# Pinscape_Pico_Expansion_Board_-_DIY_Frie.net
KiCad netlist of a schematic drawn in EAGLE
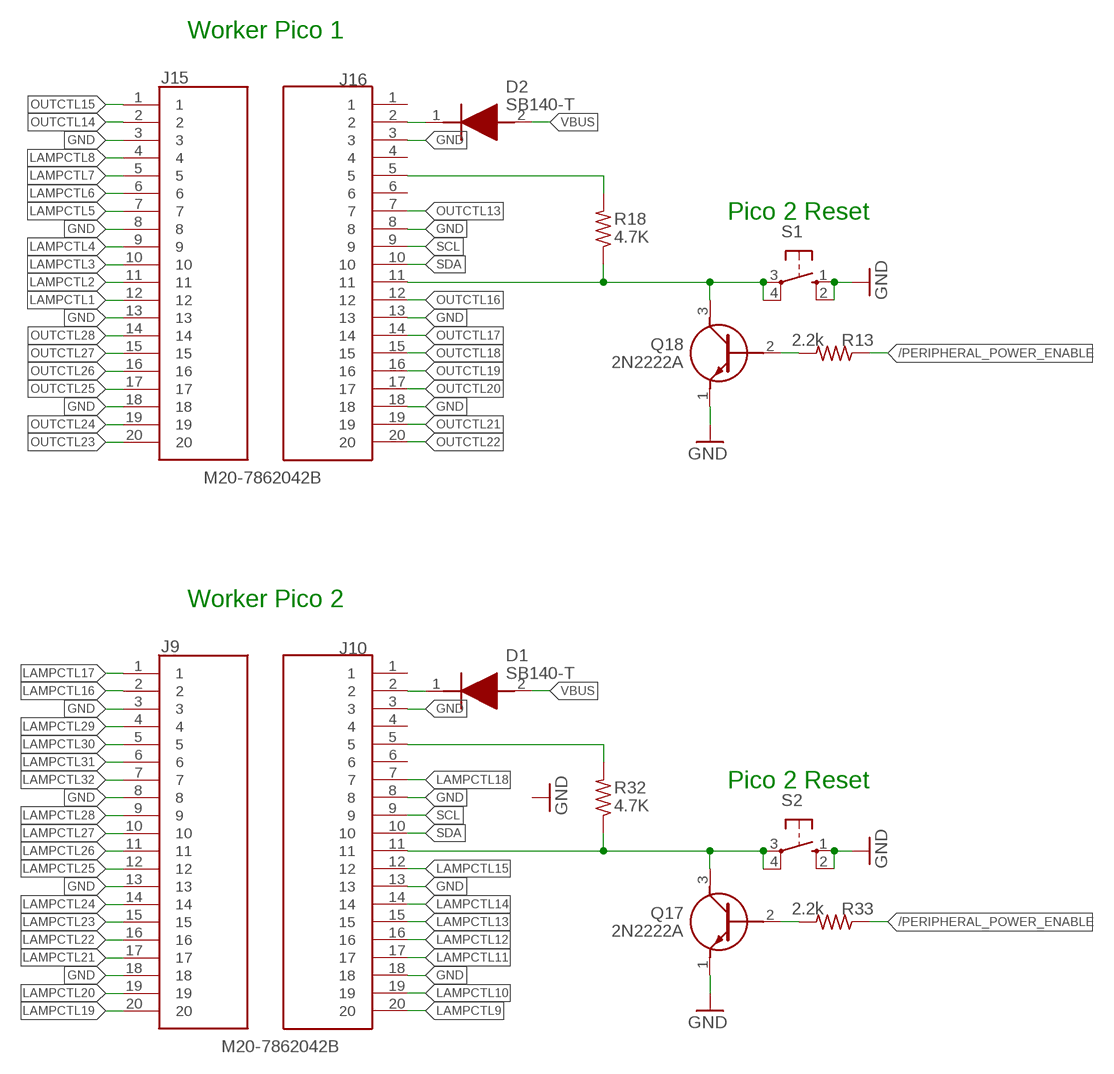
[diagram p0: schematic, sheet 1]
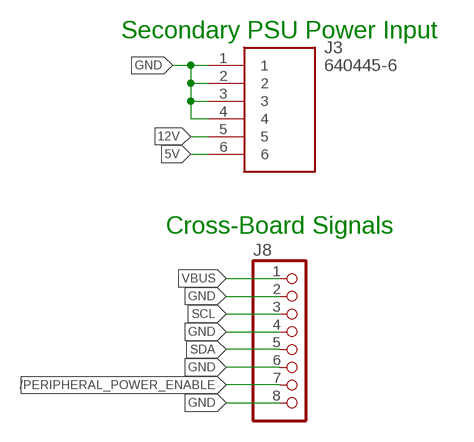
[diagram p1: schematic, sheet 2]
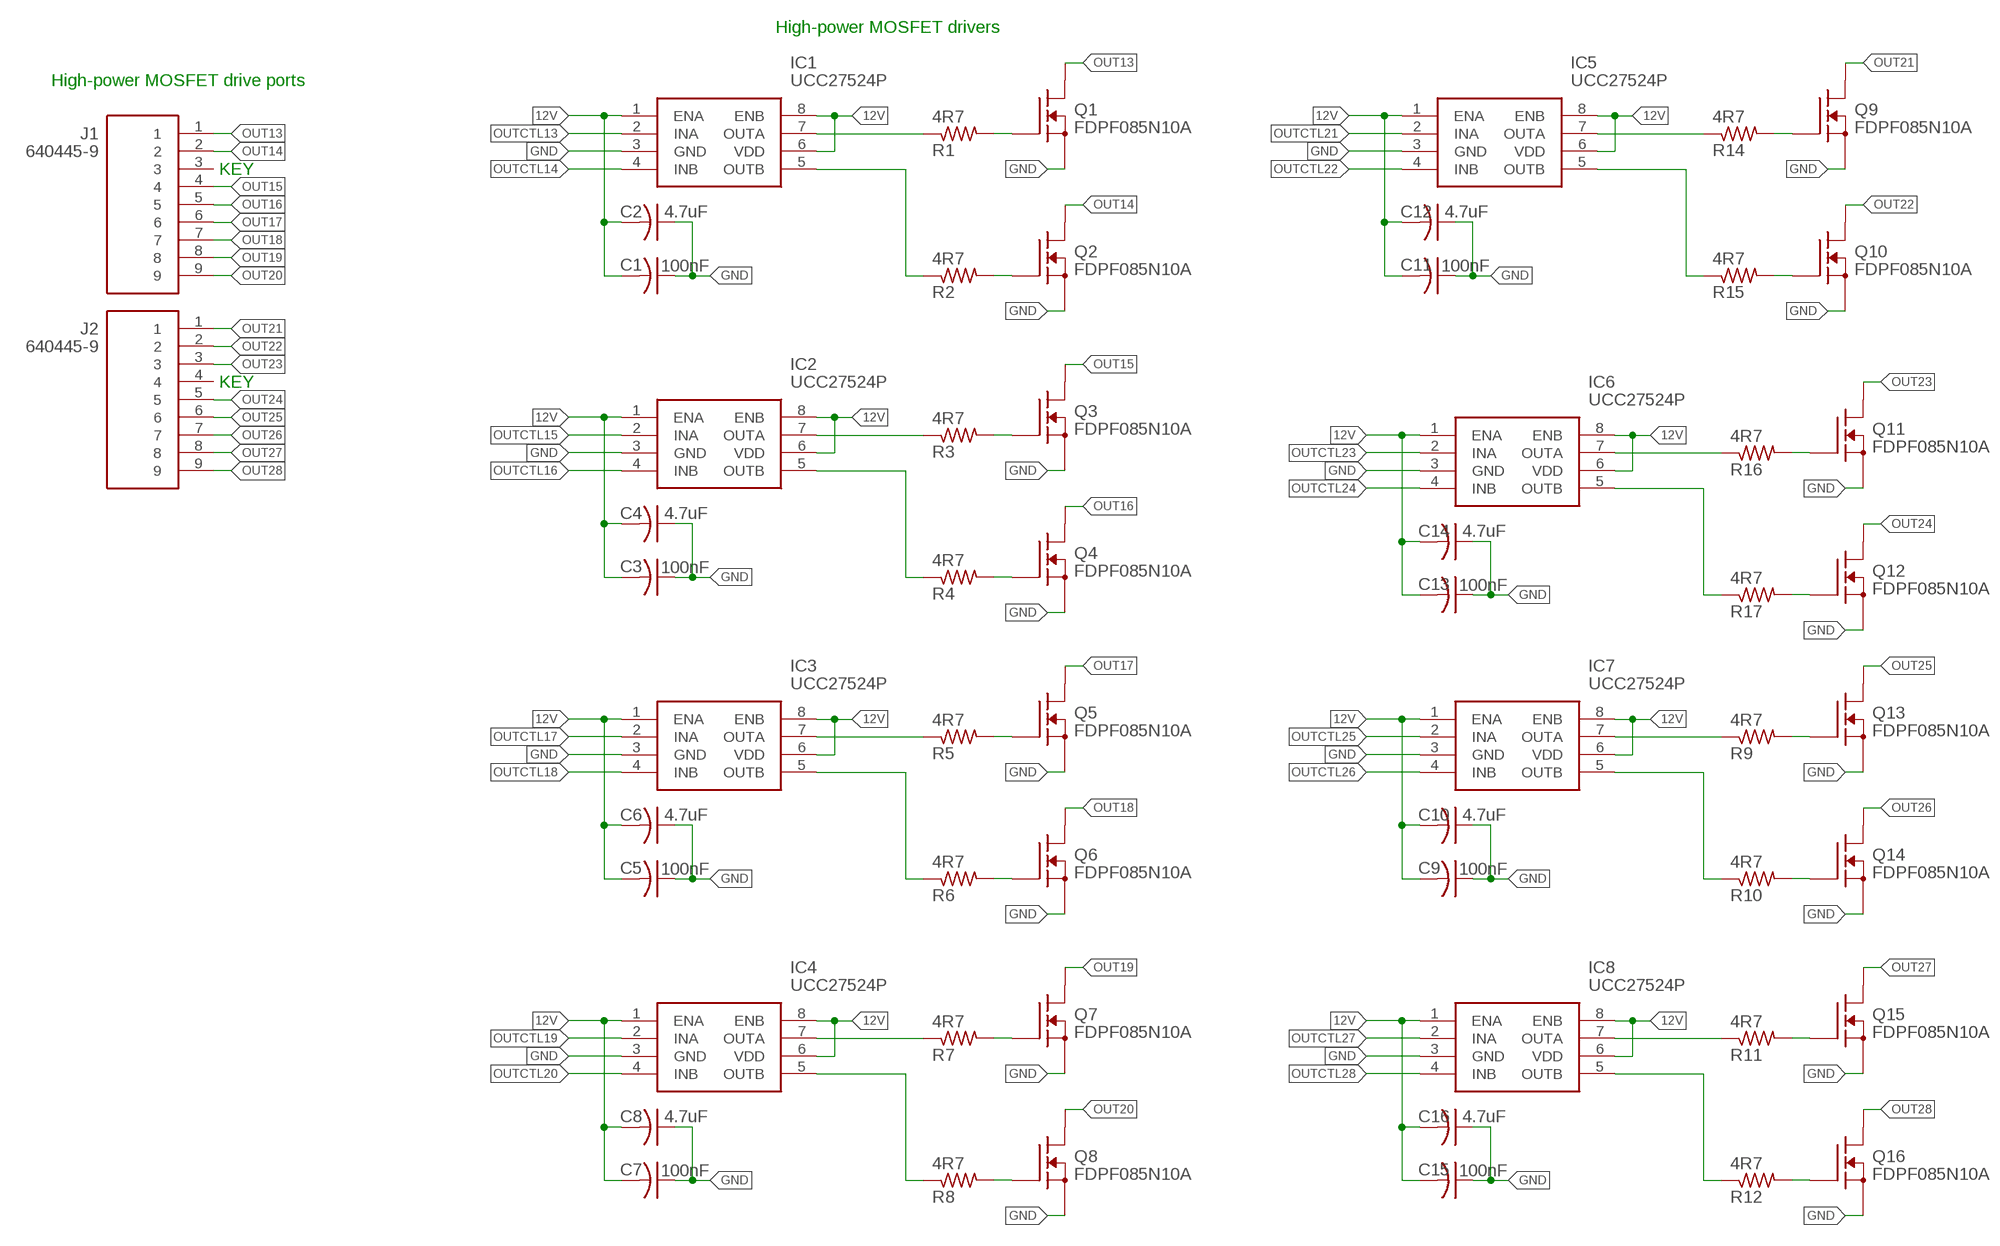
[diagram p2: schematic, sheet 3]
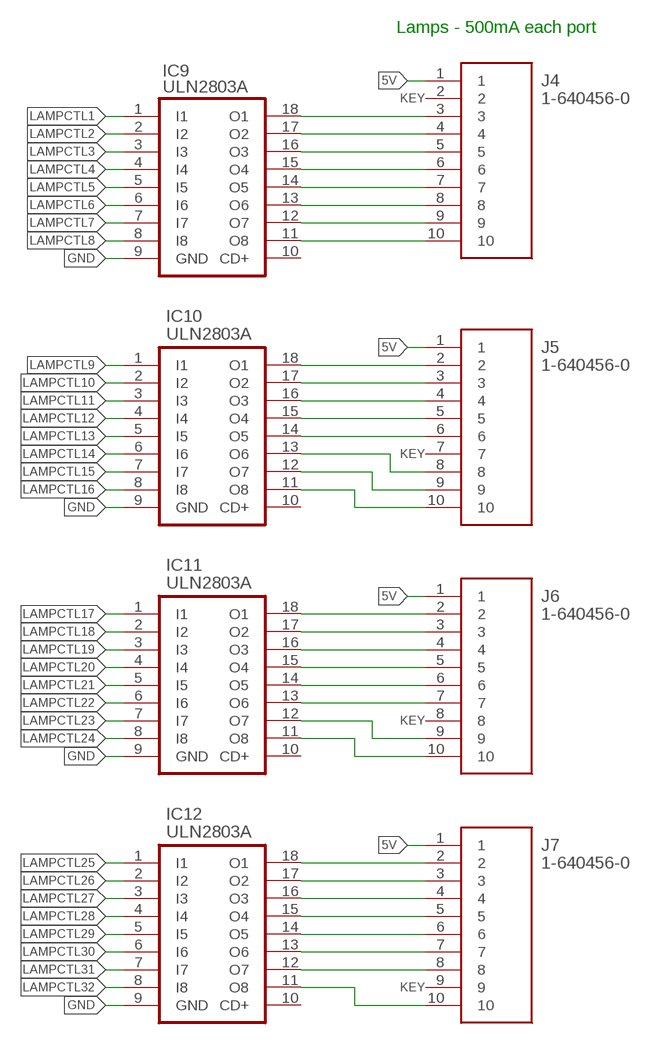
[diagram p3: schematic, sheet 4]
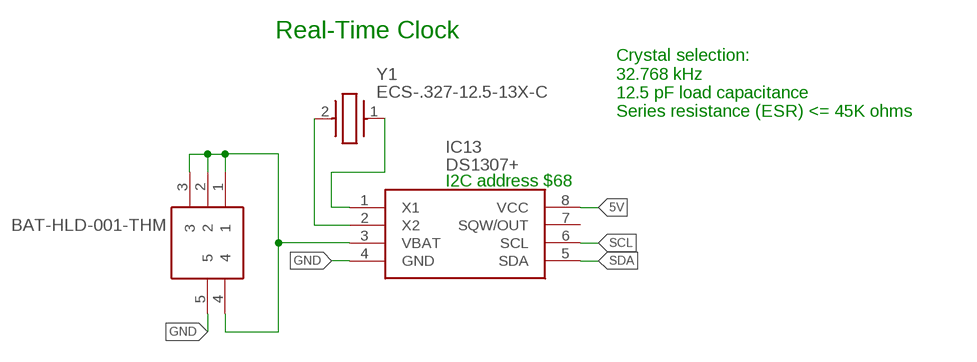
[diagram p4: schematic, sheet 5]

(export (version "E")
  (design (tool "Eeschema 10.0.6"))
  (components
    (comp (ref "J3")
      (value "640445-6")
      (footprint "eagle-import:SHDR6W183P0X396_1X6_2377X762X1")
      (fields (field (name "MOUSER_PART_NUMBER") "571-6404456"))
      (libsource (lib "eagle-import") (part "640445-6"))
    )
    (comp (ref "J8")
      (value "PINHD-1X8/90")
      (footprint "eagle-import:1X08_90")
      (libsource (lib "eagle-import") (part "PINHD-1X8/90"))
    )
    (comp (ref "BATT1")
      (value "BAT-HLD-001-THM")
      (footprint "eagle-import:BATHLD001THM")
      (fields (field (name "MOUSER_PART_NUMBER") "712-BAT-HLD-001-THM"))
      (libsource (lib "eagle-import") (part "BAT-HLD-001-THM"))
    )
    (comp (ref "IC13")
      (value "DS1307+")
      (footprint "eagle-import:DIP794W56P254L938H457Q8N")
      (fields (field (name "MOUSER_PART_NUMBER") "700-DS1307"))
      (libsource (lib "eagle-import") (part "DS1307+"))
    )
    (comp (ref "Y1")
      (value "ECS-.327-12.5-13X-C")
      (footprint "eagle-import:ECS32712513XC")
      (fields (field (name "MOUSER_PART_NUMBER") "520-S-.32712.513XC"))
      (libsource (lib "eagle-import") (part "ECS-.327-12.5-13X-C"))
    )
    (comp (ref "IC9")
      (value "ULN2803A")
      (footprint "eagle-import:DIL18")
      (libsource (lib "eagle-import") (part "ULN2803A"))
    )
    (comp (ref "IC10")
      (value "ULN2803A")
      (footprint "eagle-import:DIL18")
      (libsource (lib "eagle-import") (part "ULN2803A"))
    )
    (comp (ref "IC11")
      (value "ULN2803A")
      (footprint "eagle-import:DIL18")
      (libsource (lib "eagle-import") (part "ULN2803A"))
    )
    (comp (ref "IC12")
      (value "ULN2803A")
      (footprint "eagle-import:DIL18")
      (libsource (lib "eagle-import") (part "ULN2803A"))
    )
    (comp (ref "J4")
      (value "1-640456-0")
      (footprint "eagle-import:SHDR10W66P0X254_1X10_2540X572X")
      (fields (field (name "MOUSER_PART_NUMBER") "571-16404560"))
      (libsource (lib "eagle-import") (part "1-640456-0"))
    )
    (comp (ref "J5")
      (value "1-640456-0")
      (footprint "eagle-import:SHDR10W66P0X254_1X10_2540X572X")
      (fields (field (name "MOUSER_PART_NUMBER") "571-16404560"))
      (libsource (lib "eagle-import") (part "1-640456-0"))
    )
    (comp (ref "J6")
      (value "1-640456-0")
      (footprint "eagle-import:SHDR10W66P0X254_1X10_2540X572X")
      (fields (field (name "MOUSER_PART_NUMBER") "571-16404560"))
      (libsource (lib "eagle-import") (part "1-640456-0"))
    )
    (comp (ref "J7")
      (value "1-640456-0")
      (footprint "eagle-import:SHDR10W66P0X254_1X10_2540X572X")
      (fields (field (name "MOUSER_PART_NUMBER") "571-16404560"))
      (libsource (lib "eagle-import") (part "1-640456-0"))
    )
    (comp (ref "C1")
      (value "100nF")
      (footprint "eagle-import:C025-024X044")
      (fields (field (name "PARTNO") "21RZ310-RC"))
      (libsource (lib "eagle-import") (part "C-US025-024X044"))
    )
    (comp (ref "C2")
      (value "4.7uF")
      (footprint "eagle-import:C025-024X044")
      (fields (field (name "PARTNO") "810-FG14X5R1H475KRT0"))
      (libsource (lib "eagle-import") (part "C-US025-024X044"))
    )
    (comp (ref "C3")
      (value "100nF")
      (footprint "eagle-import:C025-024X044")
      (fields (field (name "PARTNO") "21RZ310-RC"))
      (libsource (lib "eagle-import") (part "C-US025-024X044"))
    )
    (comp (ref "C4")
      (value "4.7uF")
      (footprint "eagle-import:C025-024X044")
      (fields (field (name "PARTNO") "810-FG14X5R1H475KRT0"))
      (libsource (lib "eagle-import") (part "C-US025-024X044"))
    )
    (comp (ref "C5")
      (value "100nF")
      (footprint "eagle-import:C025-024X044")
      (fields (field (name "PARTNO") "21RZ310-RC"))
      (libsource (lib "eagle-import") (part "C-US025-024X044"))
    )
    (comp (ref "C6")
      (value "4.7uF")
      (footprint "eagle-import:C025-024X044")
      (fields (field (name "PARTNO") "810-FG14X5R1H475KRT0"))
      (libsource (lib "eagle-import") (part "C-US025-024X044"))
    )
    (comp (ref "C7")
      (value "100nF")
      (footprint "eagle-import:C025-024X044")
      (fields (field (name "PARTNO") "21RZ310-RC"))
      (libsource (lib "eagle-import") (part "C-US025-024X044"))
    )
    (comp (ref "C8")
      (value "4.7uF")
      (footprint "eagle-import:C025-024X044")
      (fields (field (name "PARTNO") "810-FG14X5R1H475KRT0"))
      (libsource (lib "eagle-import") (part "C-US025-024X044"))
    )
    (comp (ref "C9")
      (value "100nF")
      (footprint "eagle-import:C025-024X044")
      (fields (field (name "PARTNO") "21RZ310-RC"))
      (libsource (lib "eagle-import") (part "C-US025-024X044"))
    )
    (comp (ref "C10")
      (value "4.7uF")
      (footprint "eagle-import:C025-024X044")
      (fields (field (name "PARTNO") "810-FG14X5R1H475KRT0"))
      (libsource (lib "eagle-import") (part "C-US025-024X044"))
    )
    (comp (ref "C11")
      (value "100nF")
      (footprint "eagle-import:C025-024X044")
      (fields (field (name "PARTNO") "21RZ310-RC"))
      (libsource (lib "eagle-import") (part "C-US025-024X044"))
    )
    (comp (ref "C12")
      (value "4.7uF")
      (footprint "eagle-import:C025-024X044")
      (fields (field (name "PARTNO") "810-FG14X5R1H475KRT0"))
      (libsource (lib "eagle-import") (part "C-US025-024X044"))
    )
    (comp (ref "C13")
      (value "100nF")
      (footprint "eagle-import:C025-024X044")
      (fields (field (name "PARTNO") "21RZ310-RC"))
      (libsource (lib "eagle-import") (part "C-US025-024X044"))
    )
    (comp (ref "C14")
      (value "4.7uF")
      (footprint "eagle-import:C025-024X044")
      (fields (field (name "PARTNO") "810-FG14X5R1H475KRT0"))
      (libsource (lib "eagle-import") (part "C-US025-024X044"))
    )
    (comp (ref "C15")
      (value "100nF")
      (footprint "eagle-import:C025-024X044")
      (fields (field (name "PARTNO") "21RZ310-RC"))
      (libsource (lib "eagle-import") (part "C-US025-024X044"))
    )
    (comp (ref "C16")
      (value "4.7uF")
      (footprint "eagle-import:C025-024X044")
      (fields (field (name "PARTNO") "810-FG14X5R1H475KRT0"))
      (libsource (lib "eagle-import") (part "C-US025-024X044"))
    )
    (comp (ref "IC1")
      (value "UCC27524P")
      (footprint "eagle-import:DIP794W53P254L959H508Q8N")
      (fields (field (name "MOUSER_PART_NUMBER") "595-UCC27524P"))
      (libsource (lib "eagle-import") (part "UCC27524P"))
    )
    (comp (ref "IC2")
      (value "UCC27524P")
      (footprint "eagle-import:DIP794W53P254L959H508Q8N")
      (fields (field (name "MOUSER_PART_NUMBER") "595-UCC27524P"))
      (libsource (lib "eagle-import") (part "UCC27524P"))
    )
    (comp (ref "IC3")
      (value "UCC27524P")
      (footprint "eagle-import:DIP794W53P254L959H508Q8N")
      (fields (field (name "MOUSER_PART_NUMBER") "595-UCC27524P"))
      (libsource (lib "eagle-import") (part "UCC27524P"))
    )
    (comp (ref "IC4")
      (value "UCC27524P")
      (footprint "eagle-import:DIP794W53P254L959H508Q8N")
      (fields (field (name "MOUSER_PART_NUMBER") "595-UCC27524P"))
      (libsource (lib "eagle-import") (part "UCC27524P"))
    )
    (comp (ref "IC5")
      (value "UCC27524P")
      (footprint "eagle-import:DIP794W53P254L959H508Q8N")
      (fields (field (name "MOUSER_PART_NUMBER") "595-UCC27524P"))
      (libsource (lib "eagle-import") (part "UCC27524P"))
    )
    (comp (ref "IC6")
      (value "UCC27524P")
      (footprint "eagle-import:DIP794W53P254L959H508Q8N")
      (fields (field (name "MOUSER_PART_NUMBER") "595-UCC27524P"))
      (libsource (lib "eagle-import") (part "UCC27524P"))
    )
    (comp (ref "IC7")
      (value "UCC27524P")
      (footprint "eagle-import:DIP794W53P254L959H508Q8N")
      (fields (field (name "MOUSER_PART_NUMBER") "595-UCC27524P"))
      (libsource (lib "eagle-import") (part "UCC27524P"))
    )
    (comp (ref "IC8")
      (value "UCC27524P")
      (footprint "eagle-import:DIP794W53P254L959H508Q8N")
      (fields (field (name "MOUSER_PART_NUMBER") "595-UCC27524P"))
      (libsource (lib "eagle-import") (part "UCC27524P"))
    )
    (comp (ref "J1")
      (value "640445-9")
      (footprint "eagle-import:SHDR9W117P0X396_1X9_3566X762X1")
      (fields (field (name "MOUSER_PART_NUMBER") "571-6404459"))
      (libsource (lib "eagle-import") (part "640445-9"))
    )
    (comp (ref "J2")
      (value "640445-9")
      (footprint "eagle-import:SHDR9W117P0X396_1X9_3566X762X1")
      (fields (field (name "MOUSER_PART_NUMBER") "571-6404459"))
      (libsource (lib "eagle-import") (part "640445-9"))
    )
    (comp (ref "Q1")
      (value "FDPF085N10A")
      (footprint "eagle-import:TO220BV")
      (libsource (lib "eagle-import") (part "BUK7575-55A"))
    )
    (comp (ref "Q2")
      (value "FDPF085N10A")
      (footprint "eagle-import:TO220BV")
      (libsource (lib "eagle-import") (part "BUK7575-55A"))
    )
    (comp (ref "Q3")
      (value "FDPF085N10A")
      (footprint "eagle-import:TO220BV")
      (libsource (lib "eagle-import") (part "BUK7575-55A"))
    )
    (comp (ref "Q4")
      (value "FDPF085N10A")
      (footprint "eagle-import:TO220BV")
      (libsource (lib "eagle-import") (part "BUK7575-55A"))
    )
    (comp (ref "Q5")
      (value "FDPF085N10A")
      (footprint "eagle-import:TO220BV")
      (libsource (lib "eagle-import") (part "BUK7575-55A"))
    )
    (comp (ref "Q6")
      (value "FDPF085N10A")
      (footprint "eagle-import:TO220BV")
      (libsource (lib "eagle-import") (part "BUK7575-55A"))
    )
    (comp (ref "Q7")
      (value "FDPF085N10A")
      (footprint "eagle-import:TO220BV")
      (libsource (lib "eagle-import") (part "BUK7575-55A"))
    )
    (comp (ref "Q8")
      (value "FDPF085N10A")
      (footprint "eagle-import:TO220BV")
      (libsource (lib "eagle-import") (part "BUK7575-55A"))
    )
    (comp (ref "Q9")
      (value "FDPF085N10A")
      (footprint "eagle-import:TO220BV")
      (libsource (lib "eagle-import") (part "BUK7575-55A"))
    )
    (comp (ref "Q10")
      (value "FDPF085N10A")
      (footprint "eagle-import:TO220BV")
      (libsource (lib "eagle-import") (part "BUK7575-55A"))
    )
    (comp (ref "Q11")
      (value "FDPF085N10A")
      (footprint "eagle-import:TO220BV")
      (libsource (lib "eagle-import") (part "BUK7575-55A"))
    )
    (comp (ref "Q12")
      (value "FDPF085N10A")
      (footprint "eagle-import:TO220BV")
      (libsource (lib "eagle-import") (part "BUK7575-55A"))
    )
    (comp (ref "Q13")
      (value "FDPF085N10A")
      (footprint "eagle-import:TO220BV")
      (libsource (lib "eagle-import") (part "BUK7575-55A"))
    )
    (comp (ref "Q14")
      (value "FDPF085N10A")
      (footprint "eagle-import:TO220BV")
      (libsource (lib "eagle-import") (part "BUK7575-55A"))
    )
    (comp (ref "Q15")
      (value "FDPF085N10A")
      (footprint "eagle-import:TO220BV")
      (libsource (lib "eagle-import") (part "BUK7575-55A"))
    )
    (comp (ref "Q16")
      (value "FDPF085N10A")
      (footprint "eagle-import:TO220BV")
      (libsource (lib "eagle-import") (part "BUK7575-55A"))
    )
    (comp (ref "R1")
      (value "4R7")
      (footprint "eagle-import:0204_5")
      (fields (field (name "PARTNO") "660-MFS1/4DCT52R47R0"))
      (libsource (lib "eagle-import") (part "R-US_0204/5"))
    )
    (comp (ref "R2")
      (value "4R7")
      (footprint "eagle-import:0204_5")
      (fields (field (name "PARTNO") "660-MFS1/4DCT52R47R0"))
      (libsource (lib "eagle-import") (part "R-US_0204/5"))
    )
    (comp (ref "R3")
      (value "4R7")
      (footprint "eagle-import:0204_5")
      (fields (field (name "PARTNO") "660-MFS1/4DCT52R47R0"))
      (libsource (lib "eagle-import") (part "R-US_0204/5"))
    )
    (comp (ref "R4")
      (value "4R7")
      (footprint "eagle-import:0204_5")
      (fields (field (name "PARTNO") "660-MFS1/4DCT52R47R0"))
      (libsource (lib "eagle-import") (part "R-US_0204/5"))
    )
    (comp (ref "R5")
      (value "4R7")
      (footprint "eagle-import:0204_5")
      (fields (field (name "PARTNO") "660-MFS1/4DCT52R47R0"))
      (libsource (lib "eagle-import") (part "R-US_0204/5"))
    )
    (comp (ref "R6")
      (value "4R7")
      (footprint "eagle-import:0204_5")
      (fields (field (name "PARTNO") "660-MFS1/4DCT52R47R0"))
      (libsource (lib "eagle-import") (part "R-US_0204/5"))
    )
    (comp (ref "R7")
      (value "4R7")
      (footprint "eagle-import:0204_5")
      (fields (field (name "PARTNO") "660-MFS1/4DCT52R47R0"))
      (libsource (lib "eagle-import") (part "R-US_0204/5"))
    )
    (comp (ref "R8")
      (value "4R7")
      (footprint "eagle-import:0204_5")
      (fields (field (name "PARTNO") "660-MFS1/4DCT52R47R0"))
      (libsource (lib "eagle-import") (part "R-US_0204/5"))
    )
    (comp (ref "R9")
      (value "4R7")
      (footprint "eagle-import:0204_5")
      (fields (field (name "PARTNO") "660-MFS1/4DCT52R47R0"))
      (libsource (lib "eagle-import") (part "R-US_0204/5"))
    )
    (comp (ref "R10")
      (value "4R7")
      (footprint "eagle-import:0204_5")
      (fields (field (name "PARTNO") "660-MFS1/4DCT52R47R0"))
      (libsource (lib "eagle-import") (part "R-US_0204/5"))
    )
    (comp (ref "R11")
      (value "4R7")
      (footprint "eagle-import:0204_5")
      (fields (field (name "PARTNO") "660-MFS1/4DCT52R47R0"))
      (libsource (lib "eagle-import") (part "R-US_0204/5"))
    )
    (comp (ref "R12")
      (value "4R7")
      (footprint "eagle-import:0204_5")
      (fields (field (name "PARTNO") "660-MFS1/4DCT52R47R0"))
      (libsource (lib "eagle-import") (part "R-US_0204/5"))
    )
    (comp (ref "R14")
      (value "4R7")
      (footprint "eagle-import:0204_5")
      (fields (field (name "PARTNO") "660-MFS1/4DCT52R47R0"))
      (libsource (lib "eagle-import") (part "R-US_0204/5"))
    )
    (comp (ref "R15")
      (value "4R7")
      (footprint "eagle-import:0204_5")
      (fields (field (name "PARTNO") "660-MFS1/4DCT52R47R0"))
      (libsource (lib "eagle-import") (part "R-US_0204/5"))
    )
    (comp (ref "R16")
      (value "4R7")
      (footprint "eagle-import:0204_5")
      (fields (field (name "PARTNO") "660-MFS1/4DCT52R47R0"))
      (libsource (lib "eagle-import") (part "R-US_0204/5"))
    )
    (comp (ref "R17")
      (value "4R7")
      (footprint "eagle-import:0204_5")
      (fields (field (name "PARTNO") "660-MFS1/4DCT52R47R0"))
      (libsource (lib "eagle-import") (part "R-US_0204/5"))
    )
    (comp (ref "D1")
      (value "SB140-T")
      (footprint "eagle-import:DIOAD1408W86L464D236")
      (fields (field (name "MOUSER_PART_NUMBER") "621-SB140-T"))
      (libsource (lib "eagle-import") (part "SB140-T"))
    )
    (comp (ref "D2")
      (value "SB140-T")
      (footprint "eagle-import:DIOAD1408W86L464D236")
      (fields (field (name "MOUSER_PART_NUMBER") "621-SB140-T"))
      (libsource (lib "eagle-import") (part "SB140-T"))
    )
    (comp (ref "J9")
      (value "M20-7862042B")
      (footprint "eagle-import:M20-7862042-B")
      (libsource (lib "eagle-import") (part "M20-7862042B"))
    )
    (comp (ref "J10")
      (value "M20-7862042B")
      (footprint "eagle-import:M20-7862042-B")
      (libsource (lib "eagle-import") (part "M20-7862042B"))
    )
    (comp (ref "J15")
      (value "M20-7862042B")
      (footprint "eagle-import:M20-7862042-B")
      (libsource (lib "eagle-import") (part "M20-7862042B"))
    )
    (comp (ref "J16")
      (value "M20-7862042B")
      (footprint "eagle-import:M20-7862042-B")
      (libsource (lib "eagle-import") (part "M20-7862042B"))
    )
    (comp (ref "Q17")
      (value "2N2222A")
      (footprint "eagle-import:2N2222A")
      (fields (field (name "MOUSER_PART_NUMBER") "637-2N2222A"))
      (libsource (lib "eagle-import") (part "2N2222A"))
    )
    (comp (ref "Q18")
      (value "2N2222A")
      (footprint "eagle-import:2N2222A")
      (fields (field (name "MOUSER_PART_NUMBER") "637-2N2222A"))
      (libsource (lib "eagle-import") (part "2N2222A"))
    )
    (comp (ref "R13")
      (value "2.2k")
      (footprint "eagle-import:0204_7")
      (fields (field (name "PARTNO") "660-MFS1/4DCT52R47R0"))
      (libsource (lib "eagle-import") (part "R-US_0204/7"))
    )
    (comp (ref "R18")
      (value "4.7K")
      (footprint "eagle-import:0204_7")
      (fields (field (name "PARTNO") "660-MFS1/4DCT52R47R0"))
      (libsource (lib "eagle-import") (part "R-US_0204/7"))
    )
    (comp (ref "R32")
      (value "4.7K")
      (footprint "eagle-import:0204_7")
      (fields (field (name "PARTNO") "660-MFS1/4DCT52R47R0"))
      (libsource (lib "eagle-import") (part "R-US_0204/7"))
    )
    (comp (ref "R33")
      (value "2.2k")
      (footprint "eagle-import:0204_7")
      (fields (field (name "PARTNO") "660-MFS1/4DCT52R47R0"))
      (libsource (lib "eagle-import") (part "R-US_0204/7"))
    )
    (comp (ref "S1")
      (value "10-XX")
      (footprint "eagle-import:B3F-10XX")
      (fields (field (name "MPN") "B3F-1000"))
      (libsource (lib "eagle-import") (part "10-XX"))
    )
    (comp (ref "S2")
      (value "10-XX")
      (footprint "eagle-import:B3F-10XX")
      (fields (field (name "MPN") "B3F-1000"))
      (libsource (lib "eagle-import") (part "10-XX"))
    )
  )
  (nets
    (net (code "1") (name "5V") (class "Default")
      (node (ref "IC13") (pin "8") (pinfunction "VCC_8") (pintype "bidirectional"))
      (node (ref "J3") (pin "6") (pinfunction "6_6") (pintype "bidirectional"))
      (node (ref "J4") (pin "1") (pinfunction "1_1") (pintype "bidirectional"))
      (node (ref "J5") (pin "1") (pinfunction "1_1") (pintype "bidirectional"))
      (node (ref "J6") (pin "1") (pinfunction "1_1") (pintype "bidirectional"))
      (node (ref "J7") (pin "1") (pinfunction "1_1") (pintype "bidirectional"))
    )
    (net (code "2") (name "12V") (class "Default")
      (node (ref "C1") (pin "2") (pinfunction "2_2") (pintype "passive"))
      (node (ref "C10") (pin "2") (pinfunction "2_2") (pintype "passive"))
      (node (ref "C11") (pin "2") (pinfunction "2_2") (pintype "passive"))
      (node (ref "C12") (pin "2") (pinfunction "2_2") (pintype "passive"))
      (node (ref "C13") (pin "2") (pinfunction "2_2") (pintype "passive"))
      (node (ref "C14") (pin "2") (pinfunction "2_2") (pintype "passive"))
      (node (ref "C15") (pin "2") (pinfunction "2_2") (pintype "passive"))
      (node (ref "C16") (pin "2") (pinfunction "2_2") (pintype "passive"))
      (node (ref "C2") (pin "2") (pinfunction "2_2") (pintype "passive"))
      (node (ref "C3") (pin "2") (pinfunction "2_2") (pintype "passive"))
      (node (ref "C4") (pin "2") (pinfunction "2_2") (pintype "passive"))
      (node (ref "C5") (pin "2") (pinfunction "2_2") (pintype "passive"))
      (node (ref "C6") (pin "2") (pinfunction "2_2") (pintype "passive"))
      (node (ref "C7") (pin "2") (pinfunction "2_2") (pintype "passive"))
      (node (ref "C8") (pin "2") (pinfunction "2_2") (pintype "passive"))
      (node (ref "C9") (pin "2") (pinfunction "2_2") (pintype "passive"))
      (node (ref "IC1") (pin "1") (pinfunction "ENA_1") (pintype "input"))
      (node (ref "IC1") (pin "6") (pinfunction "VDD_6") (pintype "power_in"))
      (node (ref "IC1") (pin "8") (pinfunction "ENB_8") (pintype "input"))
      (node (ref "IC2") (pin "1") (pinfunction "ENA_1") (pintype "input"))
      (node (ref "IC2") (pin "6") (pinfunction "VDD_6") (pintype "power_in"))
      (node (ref "IC2") (pin "8") (pinfunction "ENB_8") (pintype "input"))
      (node (ref "IC3") (pin "1") (pinfunction "ENA_1") (pintype "input"))
      (node (ref "IC3") (pin "6") (pinfunction "VDD_6") (pintype "power_in"))
      (node (ref "IC3") (pin "8") (pinfunction "ENB_8") (pintype "input"))
      (node (ref "IC4") (pin "1") (pinfunction "ENA_1") (pintype "input"))
      (node (ref "IC4") (pin "6") (pinfunction "VDD_6") (pintype "power_in"))
      (node (ref "IC4") (pin "8") (pinfunction "ENB_8") (pintype "input"))
      (node (ref "IC5") (pin "1") (pinfunction "ENA_1") (pintype "input"))
      (node (ref "IC5") (pin "6") (pinfunction "VDD_6") (pintype "power_in"))
      (node (ref "IC5") (pin "8") (pinfunction "ENB_8") (pintype "input"))
      (node (ref "IC6") (pin "1") (pinfunction "ENA_1") (pintype "input"))
      (node (ref "IC6") (pin "6") (pinfunction "VDD_6") (pintype "power_in"))
      (node (ref "IC6") (pin "8") (pinfunction "ENB_8") (pintype "input"))
      (node (ref "IC7") (pin "1") (pinfunction "ENA_1") (pintype "input"))
      (node (ref "IC7") (pin "6") (pinfunction "VDD_6") (pintype "power_in"))
      (node (ref "IC7") (pin "8") (pinfunction "ENB_8") (pintype "input"))
      (node (ref "IC8") (pin "1") (pinfunction "ENA_1") (pintype "input"))
      (node (ref "IC8") (pin "6") (pinfunction "VDD_6") (pintype "power_in"))
      (node (ref "IC8") (pin "8") (pinfunction "ENB_8") (pintype "input"))
      (node (ref "J3") (pin "5") (pinfunction "5_5") (pintype "bidirectional"))
    )
    (net (code "3") (name "GND") (class "Default")
      (node (ref "BATT1") (pin "5") (pinfunction "5_5") (pintype "bidirectional"))
      (node (ref "C1") (pin "1") (pinfunction "1_1") (pintype "passive"))
      (node (ref "C10") (pin "1") (pinfunction "1_1") (pintype "passive"))
      (node (ref "C11") (pin "1") (pinfunction "1_1") (pintype "passive"))
      (node (ref "C12") (pin "1") (pinfunction "1_1") (pintype "passive"))
      (node (ref "C13") (pin "1") (pinfunction "1_1") (pintype "passive"))
      (node (ref "C14") (pin "1") (pinfunction "1_1") (pintype "passive"))
      (node (ref "C15") (pin "1") (pinfunction "1_1") (pintype "passive"))
      (node (ref "C16") (pin "1") (pinfunction "1_1") (pintype "passive"))
      (node (ref "C2") (pin "1") (pinfunction "1_1") (pintype "passive"))
      (node (ref "C3") (pin "1") (pinfunction "1_1") (pintype "passive"))
      (node (ref "C4") (pin "1") (pinfunction "1_1") (pintype "passive"))
      (node (ref "C5") (pin "1") (pinfunction "1_1") (pintype "passive"))
      (node (ref "C6") (pin "1") (pinfunction "1_1") (pintype "passive"))
      (node (ref "C7") (pin "1") (pinfunction "1_1") (pintype "passive"))
      (node (ref "C8") (pin "1") (pinfunction "1_1") (pintype "passive"))
      (node (ref "C9") (pin "1") (pinfunction "1_1") (pintype "passive"))
      (node (ref "IC1") (pin "3") (pinfunction "GND_3") (pintype "power_in"))
      (node (ref "IC10") (pin "9") (pinfunction "GND_9") (pintype "power_in"))
      (node (ref "IC11") (pin "9") (pinfunction "GND_9") (pintype "power_in"))
      (node (ref "IC12") (pin "9") (pinfunction "GND_9") (pintype "power_in"))
      (node (ref "IC13") (pin "4") (pinfunction "GND_4") (pintype "bidirectional"))
      (node (ref "IC2") (pin "3") (pinfunction "GND_3") (pintype "power_in"))
      (node (ref "IC3") (pin "3") (pinfunction "GND_3") (pintype "power_in"))
      (node (ref "IC4") (pin "3") (pinfunction "GND_3") (pintype "power_in"))
      (node (ref "IC5") (pin "3") (pinfunction "GND_3") (pintype "power_in"))
      (node (ref "IC6") (pin "3") (pinfunction "GND_3") (pintype "power_in"))
      (node (ref "IC7") (pin "3") (pinfunction "GND_3") (pintype "power_in"))
      (node (ref "IC8") (pin "3") (pinfunction "GND_3") (pintype "power_in"))
      (node (ref "IC9") (pin "9") (pinfunction "GND_9") (pintype "power_in"))
      (node (ref "J10") (pin "13") (pinfunction "13_13") (pintype "bidirectional"))
      (node (ref "J10") (pin "18") (pinfunction "18_18") (pintype "bidirectional"))
      (node (ref "J10") (pin "3") (pinfunction "3_3") (pintype "bidirectional"))
      (node (ref "J10") (pin "8") (pinfunction "8_8") (pintype "bidirectional"))
      (node (ref "J15") (pin "13") (pinfunction "13_13") (pintype "bidirectional"))
      (node (ref "J15") (pin "18") (pinfunction "18_18") (pintype "bidirectional"))
      (node (ref "J15") (pin "3") (pinfunction "3_3") (pintype "bidirectional"))
      (node (ref "J15") (pin "8") (pinfunction "8_8") (pintype "bidirectional"))
      (node (ref "J16") (pin "13") (pinfunction "13_13") (pintype "bidirectional"))
      (node (ref "J16") (pin "18") (pinfunction "18_18") (pintype "bidirectional"))
      (node (ref "J16") (pin "3") (pinfunction "3_3") (pintype "bidirectional"))
      (node (ref "J16") (pin "8") (pinfunction "8_8") (pintype "bidirectional"))
      (node (ref "J3") (pin "1") (pinfunction "1_1") (pintype "bidirectional"))
      (node (ref "J3") (pin "2") (pinfunction "2_2") (pintype "bidirectional"))
      (node (ref "J3") (pin "3") (pinfunction "3_3") (pintype "bidirectional"))
      (node (ref "J3") (pin "4") (pinfunction "4_4") (pintype "bidirectional"))
      (node (ref "J8") (pin "2") (pinfunction "2_2") (pintype "passive"))
      (node (ref "J8") (pin "4") (pinfunction "4_4") (pintype "passive"))
      (node (ref "J8") (pin "6") (pinfunction "6_6") (pintype "passive"))
      (node (ref "J8") (pin "8") (pinfunction "8_8") (pintype "passive"))
      (node (ref "J9") (pin "13") (pinfunction "13_13") (pintype "bidirectional"))
      (node (ref "J9") (pin "18") (pinfunction "18_18") (pintype "bidirectional"))
      (node (ref "J9") (pin "3") (pinfunction "3_3") (pintype "bidirectional"))
      (node (ref "J9") (pin "8") (pinfunction "8_8") (pintype "bidirectional"))
      (node (ref "Q1") (pin "3") (pinfunction "S_3") (pintype "passive"))
      (node (ref "Q10") (pin "3") (pinfunction "S_3") (pintype "passive"))
      (node (ref "Q11") (pin "3") (pinfunction "S_3") (pintype "passive"))
      (node (ref "Q12") (pin "3") (pinfunction "S_3") (pintype "passive"))
      (node (ref "Q13") (pin "3") (pinfunction "S_3") (pintype "passive"))
      (node (ref "Q14") (pin "3") (pinfunction "S_3") (pintype "passive"))
      (node (ref "Q15") (pin "3") (pinfunction "S_3") (pintype "passive"))
      (node (ref "Q16") (pin "3") (pinfunction "S_3") (pintype "passive"))
      (node (ref "Q17") (pin "1") (pinfunction "E_1") (pintype "bidirectional"))
      (node (ref "Q18") (pin "1") (pinfunction "E_1") (pintype "bidirectional"))
      (node (ref "Q2") (pin "3") (pinfunction "S_3") (pintype "passive"))
      (node (ref "Q3") (pin "3") (pinfunction "S_3") (pintype "passive"))
      (node (ref "Q4") (pin "3") (pinfunction "S_3") (pintype "passive"))
      (node (ref "Q5") (pin "3") (pinfunction "S_3") (pintype "passive"))
      (node (ref "Q6") (pin "3") (pinfunction "S_3") (pintype "passive"))
      (node (ref "Q7") (pin "3") (pinfunction "S_3") (pintype "passive"))
      (node (ref "Q8") (pin "3") (pinfunction "S_3") (pintype "passive"))
      (node (ref "Q9") (pin "3") (pinfunction "S_3") (pintype "passive"))
      (node (ref "S1") (pin "1") (pinfunction "S_1") (pintype "passive"))
      (node (ref "S1") (pin "2") (pinfunction "S1_2") (pintype "passive"))
      (node (ref "S2") (pin "1") (pinfunction "S_1") (pintype "passive"))
      (node (ref "S2") (pin "2") (pinfunction "S1_2") (pintype "passive"))
    )
    (net (code "4") (name "LAMPCTL1") (class "Default")
      (node (ref "IC9") (pin "1") (pinfunction "I1_1") (pintype "input"))
      (node (ref "J15") (pin "12") (pinfunction "12_12") (pintype "bidirectional"))
    )
    (net (code "5") (name "LAMPCTL2") (class "Default")
      (node (ref "IC9") (pin "2") (pinfunction "I2_2") (pintype "input"))
      (node (ref "J15") (pin "11") (pinfunction "11_11") (pintype "bidirectional"))
    )
    (net (code "6") (name "LAMPCTL3") (class "Default")
      (node (ref "IC9") (pin "3") (pinfunction "I3_3") (pintype "input"))
      (node (ref "J15") (pin "10") (pinfunction "10_10") (pintype "bidirectional"))
    )
    (net (code "7") (name "LAMPCTL4") (class "Default")
      (node (ref "IC9") (pin "4") (pinfunction "I4_4") (pintype "input"))
      (node (ref "J15") (pin "9") (pinfunction "9_9") (pintype "bidirectional"))
    )
    (net (code "8") (name "LAMPCTL5") (class "Default")
      (node (ref "IC9") (pin "5") (pinfunction "I5_5") (pintype "input"))
      (node (ref "J15") (pin "7") (pinfunction "7_7") (pintype "bidirectional"))
    )
    (net (code "9") (name "LAMPCTL6") (class "Default")
      (node (ref "IC9") (pin "6") (pinfunction "I6_6") (pintype "input"))
      (node (ref "J15") (pin "6") (pinfunction "6_6") (pintype "bidirectional"))
    )
    (net (code "10") (name "LAMPCTL7") (class "Default")
      (node (ref "IC9") (pin "7") (pinfunction "I7_7") (pintype "input"))
      (node (ref "J15") (pin "5") (pinfunction "5_5") (pintype "bidirectional"))
    )
    (net (code "11") (name "LAMPCTL8") (class "Default")
      (node (ref "IC9") (pin "8") (pinfunction "I8_8") (pintype "input"))
      (node (ref "J15") (pin "4") (pinfunction "4_4") (pintype "bidirectional"))
    )
    (net (code "12") (name "LAMPCTL9") (class "Default")
      (node (ref "IC10") (pin "1") (pinfunction "I1_1") (pintype "input"))
      (node (ref "J10") (pin "20") (pinfunction "20_20") (pintype "bidirectional"))
    )
    (net (code "13") (name "LAMPCTL10") (class "Default")
      (node (ref "IC10") (pin "2") (pinfunction "I2_2") (pintype "input"))
      (node (ref "J10") (pin "19") (pinfunction "19_19") (pintype "bidirectional"))
    )
    (net (code "14") (name "LAMPCTL11") (class "Default")
      (node (ref "IC10") (pin "3") (pinfunction "I3_3") (pintype "input"))
      (node (ref "J10") (pin "17") (pinfunction "17_17") (pintype "bidirectional"))
    )
    (net (code "15") (name "LAMPCTL12") (class "Default")
      (node (ref "IC10") (pin "4") (pinfunction "I4_4") (pintype "input"))
      (node (ref "J10") (pin "16") (pinfunction "16_16") (pintype "bidirectional"))
    )
    (net (code "16") (name "LAMPCTL13") (class "Default")
      (node (ref "IC10") (pin "5") (pinfunction "I5_5") (pintype "input"))
      (node (ref "J10") (pin "15") (pinfunction "15_15") (pintype "bidirectional"))
    )
    (net (code "17") (name "LAMPCTL14") (class "Default")
      (node (ref "IC10") (pin "6") (pinfunction "I6_6") (pintype "input"))
      (node (ref "J10") (pin "14") (pinfunction "14_14") (pintype "bidirectional"))
    )
    (net (code "18") (name "LAMPCTL15") (class "Default")
      (node (ref "IC10") (pin "7") (pinfunction "I7_7") (pintype "input"))
      (node (ref "J10") (pin "12") (pinfunction "12_12") (pintype "bidirectional"))
    )
    (net (code "19") (name "LAMPCTL16") (class "Default")
      (node (ref "IC10") (pin "8") (pinfunction "I8_8") (pintype "input"))
      (node (ref "J9") (pin "2") (pinfunction "2_2") (pintype "bidirectional"))
    )
    (net (code "20") (name "LAMPCTL17") (class "Default")
      (node (ref "IC11") (pin "1") (pinfunction "I1_1") (pintype "input"))
      (node (ref "J9") (pin "1") (pinfunction "1_1") (pintype "bidirectional"))
    )
    (net (code "21") (name "LAMPCTL18") (class "Default")
      (node (ref "IC11") (pin "2") (pinfunction "I2_2") (pintype "input"))
      (node (ref "J10") (pin "7") (pinfunction "7_7") (pintype "bidirectional"))
    )
    (net (code "22") (name "LAMPCTL19") (class "Default")
      (node (ref "IC11") (pin "3") (pinfunction "I3_3") (pintype "input"))
      (node (ref "J9") (pin "20") (pinfunction "20_20") (pintype "bidirectional"))
    )
    (net (code "23") (name "LAMPCTL20") (class "Default")
      (node (ref "IC11") (pin "4") (pinfunction "I4_4") (pintype "input"))
      (node (ref "J9") (pin "19") (pinfunction "19_19") (pintype "bidirectional"))
    )
    (net (code "24") (name "LAMPCTL21") (class "Default")
      (node (ref "IC11") (pin "5") (pinfunction "I5_5") (pintype "input"))
      (node (ref "J9") (pin "17") (pinfunction "17_17") (pintype "bidirectional"))
    )
    (net (code "25") (name "LAMPCTL22") (class "Default")
      (node (ref "IC11") (pin "6") (pinfunction "I6_6") (pintype "input"))
      (node (ref "J9") (pin "16") (pinfunction "16_16") (pintype "bidirectional"))
    )
    (net (code "26") (name "LAMPCTL23") (class "Default")
      (node (ref "IC11") (pin "7") (pinfunction "I7_7") (pintype "input"))
      (node (ref "J9") (pin "15") (pinfunction "15_15") (pintype "bidirectional"))
    )
    (net (code "27") (name "LAMPCTL24") (class "Default")
      (node (ref "IC11") (pin "8") (pinfunction "I8_8") (pintype "input"))
      (node (ref "J9") (pin "14") (pinfunction "14_14") (pintype "bidirectional"))
    )
    (net (code "28") (name "LAMPCTL25") (class "Default")
      (node (ref "IC12") (pin "1") (pinfunction "I1_1") (pintype "input"))
      (node (ref "J9") (pin "12") (pinfunction "12_12") (pintype "bidirectional"))
    )
    (net (code "29") (name "LAMPCTL26") (class "Default")
      (node (ref "IC12") (pin "2") (pinfunction "I2_2") (pintype "input"))
      (node (ref "J9") (pin "11") (pinfunction "11_11") (pintype "bidirectional"))
    )
    (net (code "30") (name "LAMPCTL27") (class "Default")
      (node (ref "IC12") (pin "3") (pinfunction "I3_3") (pintype "input"))
      (node (ref "J9") (pin "10") (pinfunction "10_10") (pintype "bidirectional"))
    )
    (net (code "31") (name "LAMPCTL28") (class "Default")
      (node (ref "IC12") (pin "4") (pinfunction "I4_4") (pintype "input"))
      (node (ref "J9") (pin "9") (pinfunction "9_9") (pintype "bidirectional"))
    )
    (net (code "32") (name "LAMPCTL29") (class "Default")
      (node (ref "IC12") (pin "5") (pinfunction "I5_5") (pintype "input"))
      (node (ref "J9") (pin "4") (pinfunction "4_4") (pintype "bidirectional"))
    )
    (net (code "33") (name "LAMPCTL30") (class "Default")
      (node (ref "IC12") (pin "6") (pinfunction "I6_6") (pintype "input"))
      (node (ref "J9") (pin "5") (pinfunction "5_5") (pintype "bidirectional"))
    )
    (net (code "34") (name "LAMPCTL31") (class "Default")
      (node (ref "IC12") (pin "7") (pinfunction "I7_7") (pintype "input"))
      (node (ref "J9") (pin "6") (pinfunction "6_6") (pintype "bidirectional"))
    )
    (net (code "35") (name "LAMPCTL32") (class "Default")
      (node (ref "IC12") (pin "8") (pinfunction "I8_8") (pintype "input"))
      (node (ref "J9") (pin "7") (pinfunction "7_7") (pintype "bidirectional"))
    )
    (net (code "36") (name "Net-(D1-K)") (class "Default")
      (node (ref "D1") (pin "1") (pinfunction "K_1") (pintype "bidirectional"))
      (node (ref "J10") (pin "2") (pinfunction "2_2") (pintype "bidirectional"))
    )
    (net (code "37") (name "Net-(D2-K)") (class "Default")
      (node (ref "D2") (pin "1") (pinfunction "K_1") (pintype "bidirectional"))
      (node (ref "J16") (pin "2") (pinfunction "2_2") (pintype "bidirectional"))
    )
    (net (code "38") (name "Net-(IC1-OUTA)") (class "Default")
      (node (ref "IC1") (pin "7") (pinfunction "OUTA_7") (pintype "output"))
      (node (ref "R1") (pin "1") (pinfunction "1_1") (pintype "passive"))
    )
    (net (code "39") (name "Net-(IC1-OUTB)") (class "Default")
      (node (ref "IC1") (pin "5") (pinfunction "OUTB_5") (pintype "output"))
      (node (ref "R2") (pin "1") (pinfunction "1_1") (pintype "passive"))
    )
    (net (code "40") (name "Net-(IC2-OUTA)") (class "Default")
      (node (ref "IC2") (pin "7") (pinfunction "OUTA_7") (pintype "output"))
      (node (ref "R3") (pin "1") (pinfunction "1_1") (pintype "passive"))
    )
    (net (code "41") (name "Net-(IC2-OUTB)") (class "Default")
      (node (ref "IC2") (pin "5") (pinfunction "OUTB_5") (pintype "output"))
      (node (ref "R4") (pin "1") (pinfunction "1_1") (pintype "passive"))
    )
    (net (code "42") (name "Net-(IC3-OUTA)") (class "Default")
      (node (ref "IC3") (pin "7") (pinfunction "OUTA_7") (pintype "output"))
      (node (ref "R5") (pin "1") (pinfunction "1_1") (pintype "passive"))
    )
    (net (code "43") (name "Net-(IC3-OUTB)") (class "Default")
      (node (ref "IC3") (pin "5") (pinfunction "OUTB_5") (pintype "output"))
      (node (ref "R6") (pin "1") (pinfunction "1_1") (pintype "passive"))
    )
    (net (code "44") (name "Net-(IC4-OUTA)") (class "Default")
      (node (ref "IC4") (pin "7") (pinfunction "OUTA_7") (pintype "output"))
      (node (ref "R7") (pin "1") (pinfunction "1_1") (pintype "passive"))
    )
    (net (code "45") (name "Net-(IC4-OUTB)") (class "Default")
      (node (ref "IC4") (pin "5") (pinfunction "OUTB_5") (pintype "output"))
      (node (ref "R8") (pin "1") (pinfunction "1_1") (pintype "passive"))
    )
    (net (code "46") (name "Net-(IC5-OUTA)") (class "Default")
      (node (ref "IC5") (pin "7") (pinfunction "OUTA_7") (pintype "output"))
      (node (ref "R14") (pin "1") (pinfunction "1_1") (pintype "passive"))
    )
    (net (code "47") (name "Net-(IC5-OUTB)") (class "Default")
      (node (ref "IC5") (pin "5") (pinfunction "OUTB_5") (pintype "output"))
      (node (ref "R15") (pin "1") (pinfunction "1_1") (pintype "passive"))
    )
    (net (code "48") (name "Net-(IC6-OUTA)") (class "Default")
      (node (ref "IC6") (pin "7") (pinfunction "OUTA_7") (pintype "output"))
      (node (ref "R16") (pin "1") (pinfunction "1_1") (pintype "passive"))
    )
    (net (code "49") (name "Net-(IC6-OUTB)") (class "Default")
      (node (ref "IC6") (pin "5") (pinfunction "OUTB_5") (pintype "output"))
      (node (ref "R17") (pin "1") (pinfunction "1_1") (pintype "passive"))
    )
    (net (code "50") (name "Net-(IC7-OUTA)") (class "Default")
      (node (ref "IC7") (pin "7") (pinfunction "OUTA_7") (pintype "output"))
      (node (ref "R9") (pin "1") (pinfunction "1_1") (pintype "passive"))
    )
    (net (code "51") (name "Net-(IC7-OUTB)") (class "Default")
      (node (ref "IC7") (pin "5") (pinfunction "OUTB_5") (pintype "output"))
      (node (ref "R10") (pin "1") (pinfunction "1_1") (pintype "passive"))
    )
    (net (code "52") (name "Net-(IC8-OUTA)") (class "Default")
      (node (ref "IC8") (pin "7") (pinfunction "OUTA_7") (pintype "output"))
      (node (ref "R11") (pin "1") (pinfunction "1_1") (pintype "passive"))
    )
    (net (code "53") (name "Net-(IC8-OUTB)") (class "Default")
      (node (ref "IC8") (pin "5") (pinfunction "OUTB_5") (pintype "output"))
      (node (ref "R12") (pin "1") (pinfunction "1_1") (pintype "passive"))
    )
    (net (code "54") (name "Net-(IC9-O1)") (class "Default")
      (node (ref "IC9") (pin "18") (pinfunction "O1_18") (pintype "open_collector"))
      (node (ref "J4") (pin "3") (pinfunction "3_3") (pintype "bidirectional"))
    )
    (net (code "55") (name "Net-(IC9-O2)") (class "Default")
      (node (ref "IC9") (pin "17") (pinfunction "O2_17") (pintype "open_collector"))
      (node (ref "J4") (pin "4") (pinfunction "4_4") (pintype "bidirectional"))
    )
    (net (code "56") (name "Net-(IC9-O3)") (class "Default")
      (node (ref "IC9") (pin "16") (pinfunction "O3_16") (pintype "open_collector"))
      (node (ref "J4") (pin "5") (pinfunction "5_5") (pintype "bidirectional"))
    )
    (net (code "57") (name "Net-(IC9-O4)") (class "Default")
      (node (ref "IC9") (pin "15") (pinfunction "O4_15") (pintype "open_collector"))
      (node (ref "J4") (pin "6") (pinfunction "6_6") (pintype "bidirectional"))
    )
    (net (code "58") (name "Net-(IC9-O5)") (class "Default")
      (node (ref "IC9") (pin "14") (pinfunction "O5_14") (pintype "open_collector"))
      (node (ref "J4") (pin "7") (pinfunction "7_7") (pintype "bidirectional"))
    )
    (net (code "59") (name "Net-(IC9-O6)") (class "Default")
      (node (ref "IC9") (pin "13") (pinfunction "O6_13") (pintype "open_collector"))
      (node (ref "J4") (pin "8") (pinfunction "8_8") (pintype "bidirectional"))
    )
    (net (code "60") (name "Net-(IC9-O7)") (class "Default")
      (node (ref "IC9") (pin "12") (pinfunction "O7_12") (pintype "open_collector"))
      (node (ref "J4") (pin "9") (pinfunction "9_9") (pintype "bidirectional"))
    )
    (net (code "61") (name "Net-(IC9-O8)") (class "Default")
      (node (ref "IC9") (pin "11") (pinfunction "O8_11") (pintype "open_collector"))
      (node (ref "J4") (pin "10") (pinfunction "10_10") (pintype "bidirectional"))
    )
    (net (code "62") (name "Net-(IC10-O1)") (class "Default")
      (node (ref "IC10") (pin "18") (pinfunction "O1_18") (pintype "open_collector"))
      (node (ref "J5") (pin "2") (pinfunction "2_2") (pintype "bidirectional"))
    )
    (net (code "63") (name "Net-(IC10-O2)") (class "Default")
      (node (ref "IC10") (pin "17") (pinfunction "O2_17") (pintype "open_collector"))
      (node (ref "J5") (pin "3") (pinfunction "3_3") (pintype "bidirectional"))
    )
    (net (code "64") (name "Net-(IC10-O3)") (class "Default")
      (node (ref "IC10") (pin "16") (pinfunction "O3_16") (pintype "open_collector"))
      (node (ref "J5") (pin "4") (pinfunction "4_4") (pintype "bidirectional"))
    )
    (net (code "65") (name "Net-(IC10-O4)") (class "Default")
      (node (ref "IC10") (pin "15") (pinfunction "O4_15") (pintype "open_collector"))
      (node (ref "J5") (pin "5") (pinfunction "5_5") (pintype "bidirectional"))
    )
    (net (code "66") (name "Net-(IC10-O5)") (class "Default")
      (node (ref "IC10") (pin "14") (pinfunction "O5_14") (pintype "open_collector"))
      (node (ref "J5") (pin "6") (pinfunction "6_6") (pintype "bidirectional"))
    )
    (net (code "67") (name "Net-(IC10-O6)") (class "Default")
      (node (ref "IC10") (pin "13") (pinfunction "O6_13") (pintype "open_collector"))
      (node (ref "J5") (pin "8") (pinfunction "8_8") (pintype "bidirectional"))
    )
    (net (code "68") (name "Net-(IC10-O7)") (class "Default")
      (node (ref "IC10") (pin "12") (pinfunction "O7_12") (pintype "open_collector"))
      (node (ref "J5") (pin "9") (pinfunction "9_9") (pintype "bidirectional"))
    )
    (net (code "69") (name "Net-(IC10-O8)") (class "Default")
      (node (ref "IC10") (pin "11") (pinfunction "O8_11") (pintype "open_collector"))
      (node (ref "J5") (pin "10") (pinfunction "10_10") (pintype "bidirectional"))
    )
    (net (code "70") (name "Net-(IC11-O1)") (class "Default")
      (node (ref "IC11") (pin "18") (pinfunction "O1_18") (pintype "open_collector"))
      (node (ref "J6") (pin "2") (pinfunction "2_2") (pintype "bidirectional"))
    )
    (net (code "71") (name "Net-(IC11-O2)") (class "Default")
      (node (ref "IC11") (pin "17") (pinfunction "O2_17") (pintype "open_collector"))
      (node (ref "J6") (pin "3") (pinfunction "3_3") (pintype "bidirectional"))
    )
    (net (code "72") (name "Net-(IC11-O3)") (class "Default")
      (node (ref "IC11") (pin "16") (pinfunction "O3_16") (pintype "open_collector"))
      (node (ref "J6") (pin "4") (pinfunction "4_4") (pintype "bidirectional"))
    )
    (net (code "73") (name "Net-(IC11-O4)") (class "Default")
      (node (ref "IC11") (pin "15") (pinfunction "O4_15") (pintype "open_collector"))
      (node (ref "J6") (pin "5") (pinfunction "5_5") (pintype "bidirectional"))
    )
    (net (code "74") (name "Net-(IC11-O5)") (class "Default")
      (node (ref "IC11") (pin "14") (pinfunction "O5_14") (pintype "open_collector"))
      (node (ref "J6") (pin "6") (pinfunction "6_6") (pintype "bidirectional"))
    )
    (net (code "75") (name "Net-(IC11-O6)") (class "Default")
      (node (ref "IC11") (pin "13") (pinfunction "O6_13") (pintype "open_collector"))
      (node (ref "J6") (pin "7") (pinfunction "7_7") (pintype "bidirectional"))
    )
    (net (code "76") (name "Net-(IC11-O7)") (class "Default")
      (node (ref "IC11") (pin "12") (pinfunction "O7_12") (pintype "open_collector"))
      (node (ref "J6") (pin "9") (pinfunction "9_9") (pintype "bidirectional"))
    )
    (net (code "77") (name "Net-(IC11-O8)") (class "Default")
      (node (ref "IC11") (pin "11") (pinfunction "O8_11") (pintype "open_collector"))
      (node (ref "J6") (pin "10") (pinfunction "10_10") (pintype "bidirectional"))
    )
    (net (code "78") (name "Net-(IC12-O1)") (class "Default")
      (node (ref "IC12") (pin "18") (pinfunction "O1_18") (pintype "open_collector"))
      (node (ref "J7") (pin "2") (pinfunction "2_2") (pintype "bidirectional"))
    )
    (net (code "79") (name "Net-(IC12-O2)") (class "Default")
      (node (ref "IC12") (pin "17") (pinfunction "O2_17") (pintype "open_collector"))
      (node (ref "J7") (pin "3") (pinfunction "3_3") (pintype "bidirectional"))
    )
    (net (code "80") (name "Net-(IC12-O3)") (class "Default")
      (node (ref "IC12") (pin "16") (pinfunction "O3_16") (pintype "open_collector"))
      (node (ref "J7") (pin "4") (pinfunction "4_4") (pintype "bidirectional"))
    )
    (net (code "81") (name "Net-(IC12-O4)") (class "Default")
      (node (ref "IC12") (pin "15") (pinfunction "O4_15") (pintype "open_collector"))
      (node (ref "J7") (pin "5") (pinfunction "5_5") (pintype "bidirectional"))
    )
    (net (code "82") (name "Net-(IC12-O5)") (class "Default")
      (node (ref "IC12") (pin "14") (pinfunction "O5_14") (pintype "open_collector"))
      (node (ref "J7") (pin "6") (pinfunction "6_6") (pintype "bidirectional"))
    )
    (net (code "83") (name "Net-(IC12-O6)") (class "Default")
      (node (ref "IC12") (pin "13") (pinfunction "O6_13") (pintype "open_collector"))
      (node (ref "J7") (pin "7") (pinfunction "7_7") (pintype "bidirectional"))
    )
    (net (code "84") (name "Net-(IC12-O7)") (class "Default")
      (node (ref "IC12") (pin "12") (pinfunction "O7_12") (pintype "open_collector"))
      (node (ref "J7") (pin "8") (pinfunction "8_8") (pintype "bidirectional"))
    )
    (net (code "85") (name "Net-(IC12-O8)") (class "Default")
      (node (ref "IC12") (pin "11") (pinfunction "O8_11") (pintype "open_collector"))
      (node (ref "J7") (pin "10") (pinfunction "10_10") (pintype "bidirectional"))
    )
    (net (code "86") (name "Net-(IC13-VBAT)") (class "Default")
      (node (ref "BATT1") (pin "1") (pinfunction "1_1") (pintype "bidirectional"))
      (node (ref "BATT1") (pin "2") (pinfunction "2_2") (pintype "bidirectional"))
      (node (ref "BATT1") (pin "3") (pinfunction "3_3") (pintype "bidirectional"))
      (node (ref "BATT1") (pin "4") (pinfunction "4_4") (pintype "bidirectional"))
      (node (ref "IC13") (pin "3") (pinfunction "VBAT_3") (pintype "bidirectional"))
    )
    (net (code "87") (name "Net-(IC13-X1)") (class "Default")
      (node (ref "IC13") (pin "1") (pinfunction "X1_1") (pintype "bidirectional"))
      (node (ref "Y1") (pin "1") (pinfunction "CRYSTAL_1_1") (pintype "bidirectional"))
    )
    (net (code "88") (name "Net-(IC13-X2)") (class "Default")
      (node (ref "IC13") (pin "2") (pinfunction "X2_2") (pintype "bidirectional"))
      (node (ref "Y1") (pin "2") (pinfunction "CRYSTAL_2_2") (pintype "bidirectional"))
    )
    (net (code "89") (name "Net-(J10-Pad5)") (class "Default")
      (node (ref "J10") (pin "5") (pinfunction "5_5") (pintype "bidirectional"))
      (node (ref "R32") (pin "2") (pinfunction "2_2") (pintype "passive"))
    )
    (net (code "90") (name "Net-(J16-Pad5)") (class "Default")
      (node (ref "J16") (pin "5") (pinfunction "5_5") (pintype "bidirectional"))
      (node (ref "R18") (pin "2") (pinfunction "2_2") (pintype "passive"))
    )
    (net (code "91") (name "Net-(Q1-G)") (class "Default")
      (node (ref "Q1") (pin "1") (pinfunction "G_1") (pintype "passive"))
      (node (ref "R1") (pin "2") (pinfunction "2_2") (pintype "passive"))
    )
    (net (code "92") (name "Net-(Q2-G)") (class "Default")
      (node (ref "Q2") (pin "1") (pinfunction "G_1") (pintype "passive"))
      (node (ref "R2") (pin "2") (pinfunction "2_2") (pintype "passive"))
    )
    (net (code "93") (name "Net-(Q3-G)") (class "Default")
      (node (ref "Q3") (pin "1") (pinfunction "G_1") (pintype "passive"))
      (node (ref "R3") (pin "2") (pinfunction "2_2") (pintype "passive"))
    )
    (net (code "94") (name "Net-(Q4-G)") (class "Default")
      (node (ref "Q4") (pin "1") (pinfunction "G_1") (pintype "passive"))
      (node (ref "R4") (pin "2") (pinfunction "2_2") (pintype "passive"))
    )
    (net (code "95") (name "Net-(Q5-G)") (class "Default")
      (node (ref "Q5") (pin "1") (pinfunction "G_1") (pintype "passive"))
      (node (ref "R5") (pin "2") (pinfunction "2_2") (pintype "passive"))
    )
    (net (code "96") (name "Net-(Q6-G)") (class "Default")
      (node (ref "Q6") (pin "1") (pinfunction "G_1") (pintype "passive"))
      (node (ref "R6") (pin "2") (pinfunction "2_2") (pintype "passive"))
    )
    (net (code "97") (name "Net-(Q7-G)") (class "Default")
      (node (ref "Q7") (pin "1") (pinfunction "G_1") (pintype "passive"))
      (node (ref "R7") (pin "2") (pinfunction "2_2") (pintype "passive"))
    )
    (net (code "98") (name "Net-(Q8-G)") (class "Default")
      (node (ref "Q8") (pin "1") (pinfunction "G_1") (pintype "passive"))
      (node (ref "R8") (pin "2") (pinfunction "2_2") (pintype "passive"))
    )
    (net (code "99") (name "Net-(Q9-G)") (class "Default")
      (node (ref "Q9") (pin "1") (pinfunction "G_1") (pintype "passive"))
      (node (ref "R14") (pin "2") (pinfunction "2_2") (pintype "passive"))
    )
    (net (code "100") (name "Net-(Q10-G)") (class "Default")
      (node (ref "Q10") (pin "1") (pinfunction "G_1") (pintype "passive"))
      (node (ref "R15") (pin "2") (pinfunction "2_2") (pintype "passive"))
    )
    (net (code "101") (name "Net-(Q11-G)") (class "Default")
      (node (ref "Q11") (pin "1") (pinfunction "G_1") (pintype "passive"))
      (node (ref "R16") (pin "2") (pinfunction "2_2") (pintype "passive"))
    )
    (net (code "102") (name "Net-(Q12-G)") (class "Default")
      (node (ref "Q12") (pin "1") (pinfunction "G_1") (pintype "passive"))
      (node (ref "R17") (pin "2") (pinfunction "2_2") (pintype "passive"))
    )
    (net (code "103") (name "Net-(Q13-G)") (class "Default")
      (node (ref "Q13") (pin "1") (pinfunction "G_1") (pintype "passive"))
      (node (ref "R9") (pin "2") (pinfunction "2_2") (pintype "passive"))
    )
    (net (code "104") (name "Net-(Q14-G)") (class "Default")
      (node (ref "Q14") (pin "1") (pinfunction "G_1") (pintype "passive"))
      (node (ref "R10") (pin "2") (pinfunction "2_2") (pintype "passive"))
    )
    (net (code "105") (name "Net-(Q15-G)") (class "Default")
      (node (ref "Q15") (pin "1") (pinfunction "G_1") (pintype "passive"))
      (node (ref "R11") (pin "2") (pinfunction "2_2") (pintype "passive"))
    )
    (net (code "106") (name "Net-(Q16-G)") (class "Default")
      (node (ref "Q16") (pin "1") (pinfunction "G_1") (pintype "passive"))
      (node (ref "R12") (pin "2") (pinfunction "2_2") (pintype "passive"))
    )
    (net (code "107") (name "Net-(Q17-B)") (class "Default")
      (node (ref "Q17") (pin "2") (pinfunction "B_2") (pintype "bidirectional"))
      (node (ref "R33") (pin "2") (pinfunction "2_2") (pintype "passive"))
    )
    (net (code "108") (name "Net-(Q17-C)") (class "Default")
      (node (ref "J10") (pin "11") (pinfunction "11_11") (pintype "bidirectional"))
      (node (ref "Q17") (pin "3") (pinfunction "C_3") (pintype "bidirectional"))
      (node (ref "R32") (pin "1") (pinfunction "1_1") (pintype "passive"))
      (node (ref "S2") (pin "3") (pinfunction "P_3") (pintype "passive"))
      (node (ref "S2") (pin "4") (pinfunction "P1_4") (pintype "passive"))
    )
    (net (code "109") (name "Net-(Q18-B)") (class "Default")
      (node (ref "Q18") (pin "2") (pinfunction "B_2") (pintype "bidirectional"))
      (node (ref "R13") (pin "2") (pinfunction "2_2") (pintype "passive"))
    )
    (net (code "110") (name "Net-(Q18-C)") (class "Default")
      (node (ref "J16") (pin "11") (pinfunction "11_11") (pintype "bidirectional"))
      (node (ref "Q18") (pin "3") (pinfunction "C_3") (pintype "bidirectional"))
      (node (ref "R18") (pin "1") (pinfunction "1_1") (pintype "passive"))
      (node (ref "S1") (pin "3") (pinfunction "P_3") (pintype "passive"))
      (node (ref "S1") (pin "4") (pinfunction "P1_4") (pintype "passive"))
    )
    (net (code "111") (name "OUT13") (class "Default")
      (node (ref "J1") (pin "1") (pinfunction "1_1") (pintype "bidirectional"))
      (node (ref "Q1") (pin "2") (pinfunction "D_2") (pintype "passive"))
    )
    (net (code "112") (name "OUT14") (class "Default")
      (node (ref "J1") (pin "2") (pinfunction "2_2") (pintype "bidirectional"))
      (node (ref "Q2") (pin "2") (pinfunction "D_2") (pintype "passive"))
    )
    (net (code "113") (name "OUT15") (class "Default")
      (node (ref "J1") (pin "4") (pinfunction "4_4") (pintype "bidirectional"))
      (node (ref "Q3") (pin "2") (pinfunction "D_2") (pintype "passive"))
    )
    (net (code "114") (name "OUT16") (class "Default")
      (node (ref "J1") (pin "5") (pinfunction "5_5") (pintype "bidirectional"))
      (node (ref "Q4") (pin "2") (pinfunction "D_2") (pintype "passive"))
    )
    (net (code "115") (name "OUT17") (class "Default")
      (node (ref "J1") (pin "6") (pinfunction "6_6") (pintype "bidirectional"))
      (node (ref "Q5") (pin "2") (pinfunction "D_2") (pintype "passive"))
    )
    (net (code "116") (name "OUT18") (class "Default")
      (node (ref "J1") (pin "7") (pinfunction "7_7") (pintype "bidirectional"))
      (node (ref "Q6") (pin "2") (pinfunction "D_2") (pintype "passive"))
    )
    (net (code "117") (name "OUT19") (class "Default")
      (node (ref "J1") (pin "8") (pinfunction "8_8") (pintype "bidirectional"))
      (node (ref "Q7") (pin "2") (pinfunction "D_2") (pintype "passive"))
    )
    (net (code "118") (name "OUT20") (class "Default")
      (node (ref "J1") (pin "9") (pinfunction "9_9") (pintype "bidirectional"))
      (node (ref "Q8") (pin "2") (pinfunction "D_2") (pintype "passive"))
    )
    (net (code "119") (name "OUT21") (class "Default")
      (node (ref "J2") (pin "1") (pinfunction "1_1") (pintype "bidirectional"))
      (node (ref "Q9") (pin "2") (pinfunction "D_2") (pintype "passive"))
    )
    (net (code "120") (name "OUT22") (class "Default")
      (node (ref "J2") (pin "2") (pinfunction "2_2") (pintype "bidirectional"))
      (node (ref "Q10") (pin "2") (pinfunction "D_2") (pintype "passive"))
    )
    (net (code "121") (name "OUT23") (class "Default")
      (node (ref "J2") (pin "3") (pinfunction "3_3") (pintype "bidirectional"))
      (node (ref "Q11") (pin "2") (pinfunction "D_2") (pintype "passive"))
    )
    (net (code "122") (name "OUT24") (class "Default")
      (node (ref "J2") (pin "5") (pinfunction "5_5") (pintype "bidirectional"))
      (node (ref "Q12") (pin "2") (pinfunction "D_2") (pintype "passive"))
    )
    (net (code "123") (name "OUT25") (class "Default")
      (node (ref "J2") (pin "6") (pinfunction "6_6") (pintype "bidirectional"))
      (node (ref "Q13") (pin "2") (pinfunction "D_2") (pintype "passive"))
    )
    (net (code "124") (name "OUT26") (class "Default")
      (node (ref "J2") (pin "7") (pinfunction "7_7") (pintype "bidirectional"))
      (node (ref "Q14") (pin "2") (pinfunction "D_2") (pintype "passive"))
    )
    (net (code "125") (name "OUT27") (class "Default")
      (node (ref "J2") (pin "8") (pinfunction "8_8") (pintype "bidirectional"))
      (node (ref "Q15") (pin "2") (pinfunction "D_2") (pintype "passive"))
    )
    (net (code "126") (name "OUT28") (class "Default")
      (node (ref "J2") (pin "9") (pinfunction "9_9") (pintype "bidirectional"))
      (node (ref "Q16") (pin "2") (pinfunction "D_2") (pintype "passive"))
    )
    (net (code "127") (name "OUTCTL13") (class "Default")
      (node (ref "IC1") (pin "2") (pinfunction "INA_2") (pintype "input"))
      (node (ref "J16") (pin "7") (pinfunction "7_7") (pintype "bidirectional"))
    )
    (net (code "128") (name "OUTCTL14") (class "Default")
      (node (ref "IC1") (pin "4") (pinfunction "INB_4") (pintype "input"))
      (node (ref "J15") (pin "2") (pinfunction "2_2") (pintype "bidirectional"))
    )
    (net (code "129") (name "OUTCTL15") (class "Default")
      (node (ref "IC2") (pin "2") (pinfunction "INA_2") (pintype "input"))
      (node (ref "J15") (pin "1") (pinfunction "1_1") (pintype "bidirectional"))
    )
    (net (code "130") (name "OUTCTL16") (class "Default")
      (node (ref "IC2") (pin "4") (pinfunction "INB_4") (pintype "input"))
      (node (ref "J16") (pin "12") (pinfunction "12_12") (pintype "bidirectional"))
    )
    (net (code "131") (name "OUTCTL17") (class "Default")
      (node (ref "IC3") (pin "2") (pinfunction "INA_2") (pintype "input"))
      (node (ref "J16") (pin "14") (pinfunction "14_14") (pintype "bidirectional"))
    )
    (net (code "132") (name "OUTCTL18") (class "Default")
      (node (ref "IC3") (pin "4") (pinfunction "INB_4") (pintype "input"))
      (node (ref "J16") (pin "15") (pinfunction "15_15") (pintype "bidirectional"))
    )
    (net (code "133") (name "OUTCTL19") (class "Default")
      (node (ref "IC4") (pin "2") (pinfunction "INA_2") (pintype "input"))
      (node (ref "J16") (pin "16") (pinfunction "16_16") (pintype "bidirectional"))
    )
    (net (code "134") (name "OUTCTL20") (class "Default")
      (node (ref "IC4") (pin "4") (pinfunction "INB_4") (pintype "input"))
      (node (ref "J16") (pin "17") (pinfunction "17_17") (pintype "bidirectional"))
    )
    (net (code "135") (name "OUTCTL21") (class "Default")
      (node (ref "IC5") (pin "2") (pinfunction "INA_2") (pintype "input"))
      (node (ref "J16") (pin "19") (pinfunction "19_19") (pintype "bidirectional"))
    )
    (net (code "136") (name "OUTCTL22") (class "Default")
      (node (ref "IC5") (pin "4") (pinfunction "INB_4") (pintype "input"))
      (node (ref "J16") (pin "20") (pinfunction "20_20") (pintype "bidirectional"))
    )
    (net (code "137") (name "OUTCTL23") (class "Default")
      (node (ref "IC6") (pin "2") (pinfunction "INA_2") (pintype "input"))
      (node (ref "J15") (pin "20") (pinfunction "20_20") (pintype "bidirectional"))
    )
    (net (code "138") (name "OUTCTL24") (class "Default")
      (node (ref "IC6") (pin "4") (pinfunction "INB_4") (pintype "input"))
      (node (ref "J15") (pin "19") (pinfunction "19_19") (pintype "bidirectional"))
    )
    (net (code "139") (name "OUTCTL25") (class "Default")
      (node (ref "IC7") (pin "2") (pinfunction "INA_2") (pintype "input"))
      (node (ref "J15") (pin "17") (pinfunction "17_17") (pintype "bidirectional"))
    )
    (net (code "140") (name "OUTCTL26") (class "Default")
      (node (ref "IC7") (pin "4") (pinfunction "INB_4") (pintype "input"))
      (node (ref "J15") (pin "16") (pinfunction "16_16") (pintype "bidirectional"))
    )
    (net (code "141") (name "OUTCTL27") (class "Default")
      (node (ref "IC8") (pin "2") (pinfunction "INA_2") (pintype "input"))
      (node (ref "J15") (pin "15") (pinfunction "15_15") (pintype "bidirectional"))
    )
    (net (code "142") (name "OUTCTL28") (class "Default")
      (node (ref "IC8") (pin "4") (pinfunction "INB_4") (pintype "input"))
      (node (ref "J15") (pin "14") (pinfunction "14_14") (pintype "bidirectional"))
    )
    (net (code "143") (name "SCL") (class "Default")
      (node (ref "IC13") (pin "6") (pinfunction "SCL_6") (pintype "bidirectional"))
      (node (ref "J10") (pin "9") (pinfunction "9_9") (pintype "bidirectional"))
      (node (ref "J16") (pin "9") (pinfunction "9_9") (pintype "bidirectional"))
      (node (ref "J8") (pin "3") (pinfunction "3_3") (pintype "passive"))
    )
    (net (code "144") (name "SDA") (class "Default")
      (node (ref "IC13") (pin "5") (pinfunction "SDA_5") (pintype "bidirectional"))
      (node (ref "J10") (pin "10") (pinfunction "10_10") (pintype "bidirectional"))
      (node (ref "J16") (pin "10") (pinfunction "10_10") (pintype "bidirectional"))
      (node (ref "J8") (pin "5") (pinfunction "5_5") (pintype "passive"))
    )
    (net (code "145") (name "VBUS") (class "Default")
      (node (ref "D1") (pin "2") (pinfunction "A_2") (pintype "bidirectional"))
      (node (ref "D2") (pin "2") (pinfunction "A_2") (pintype "bidirectional"))
      (node (ref "J8") (pin "1") (pinfunction "1_1") (pintype "passive"))
    )
    (net (code "146") (name "unconnected-(IC9-CD+-Pad10)") (class "Default")
      (node (ref "IC9") (pin "10") (pinfunction "CD+_10") (pintype "passive"))
    )
    (net (code "147") (name "unconnected-(IC10-CD+-Pad10)") (class "Default")
      (node (ref "IC10") (pin "10") (pinfunction "CD+_10") (pintype "passive"))
    )
    (net (code "148") (name "unconnected-(IC11-CD+-Pad10)") (class "Default")
      (node (ref "IC11") (pin "10") (pinfunction "CD+_10") (pintype "passive"))
    )
    (net (code "149") (name "unconnected-(IC12-CD+-Pad10)") (class "Default")
      (node (ref "IC12") (pin "10") (pinfunction "CD+_10") (pintype "passive"))
    )
    (net (code "150") (name "unconnected-(IC13-SQW{slash}OUT-Pad7)") (class "Default")
      (node (ref "IC13") (pin "7") (pinfunction "SQW/OUT_7") (pintype "bidirectional"))
    )
    (net (code "151") (name "unconnected-(J1-Pad3)") (class "Default")
      (node (ref "J1") (pin "3") (pinfunction "3_3") (pintype "bidirectional"))
    )
    (net (code "152") (name "unconnected-(J2-Pad4)") (class "Default")
      (node (ref "J2") (pin "4") (pinfunction "4_4") (pintype "bidirectional"))
    )
    (net (code "153") (name "unconnected-(J4-Pad2)") (class "Default")
      (node (ref "J4") (pin "2") (pinfunction "2_2") (pintype "bidirectional"))
    )
    (net (code "154") (name "unconnected-(J5-Pad7)") (class "Default")
      (node (ref "J5") (pin "7") (pinfunction "7_7") (pintype "bidirectional"))
    )
    (net (code "155") (name "unconnected-(J6-Pad8)") (class "Default")
      (node (ref "J6") (pin "8") (pinfunction "8_8") (pintype "bidirectional"))
    )
    (net (code "156") (name "unconnected-(J7-Pad9)") (class "Default")
      (node (ref "J7") (pin "9") (pinfunction "9_9") (pintype "bidirectional"))
    )
    (net (code "157") (name "unconnected-(J10-Pad1)") (class "Default")
      (node (ref "J10") (pin "1") (pinfunction "1_1") (pintype "bidirectional"))
    )
    (net (code "158") (name "unconnected-(J10-Pad4)") (class "Default")
      (node (ref "J10") (pin "4") (pinfunction "4_4") (pintype "bidirectional"))
    )
    (net (code "159") (name "unconnected-(J10-Pad6)") (class "Default")
      (node (ref "J10") (pin "6") (pinfunction "6_6") (pintype "bidirectional"))
    )
    (net (code "160") (name "unconnected-(J16-Pad1)") (class "Default")
      (node (ref "J16") (pin "1") (pinfunction "1_1") (pintype "bidirectional"))
    )
    (net (code "161") (name "unconnected-(J16-Pad4)") (class "Default")
      (node (ref "J16") (pin "4") (pinfunction "4_4") (pintype "bidirectional"))
    )
    (net (code "162") (name "unconnected-(J16-Pad6)") (class "Default")
      (node (ref "J16") (pin "6") (pinfunction "6_6") (pintype "bidirectional"))
    )
    (net (code "163") (name "{slash}PERIPHERAL_POWER_ENABLE") (class "Default")
      (node (ref "J8") (pin "7") (pinfunction "7_7") (pintype "passive"))
      (node (ref "R13") (pin "1") (pinfunction "1_1") (pintype "passive"))
      (node (ref "R33") (pin "1") (pinfunction "1_1") (pintype "passive"))
    )
  )
)
